# FEU-102-1_part1.net
KiCad netlist of a schematic drawn in Altium Designer
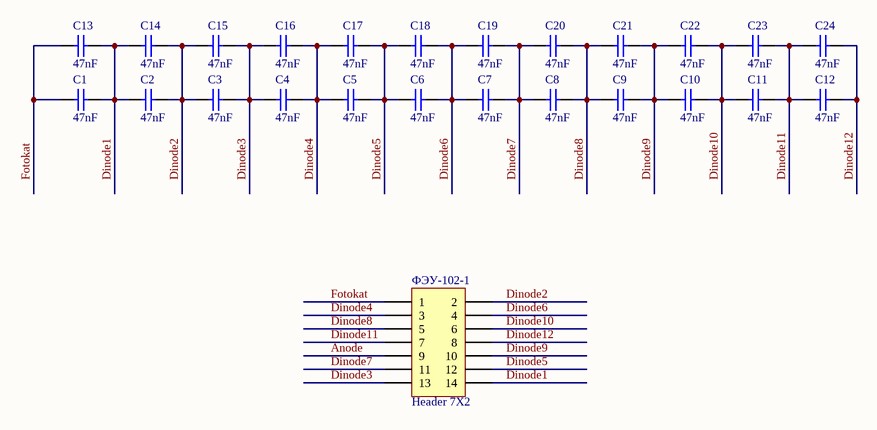
[diagram p0: FEU-102-1_part1.SchDoc]

(export (version "E")
  (design (tool "Eeschema 10.0.6"))
  (components
    (comp (ref "C1")
      (value "47nF")
      (footprint "0805_CAP")
      (description "Capacitor (Semiconductor SIM Model)")
      (fields (field (name "PUBLISHER") "Altium Limited"))
      (libsource (lib "Miscellaneous Devices") (part "Cap Semi"))
    )
    (comp (ref "C2")
      (value "47nF")
      (footprint "0805_CAP")
      (description "Capacitor (Semiconductor SIM Model)")
      (fields (field (name "PUBLISHER") "Altium Limited"))
      (libsource (lib "Miscellaneous Devices") (part "Cap Semi"))
    )
    (comp (ref "C3")
      (value "47nF")
      (footprint "0805_CAP")
      (description "Capacitor (Semiconductor SIM Model)")
      (fields (field (name "PUBLISHER") "Altium Limited"))
      (libsource (lib "Miscellaneous Devices") (part "Cap Semi"))
    )
    (comp (ref "C4")
      (value "47nF")
      (footprint "0805_CAP")
      (description "Capacitor (Semiconductor SIM Model)")
      (fields (field (name "PUBLISHER") "Altium Limited"))
      (libsource (lib "Miscellaneous Devices") (part "Cap Semi"))
    )
    (comp (ref "C5")
      (value "47nF")
      (footprint "0805_CAP")
      (description "Capacitor (Semiconductor SIM Model)")
      (fields (field (name "PUBLISHER") "Altium Limited"))
      (libsource (lib "Miscellaneous Devices") (part "Cap Semi"))
    )
    (comp (ref "C6")
      (value "47nF")
      (footprint "0805_CAP")
      (description "Capacitor (Semiconductor SIM Model)")
      (fields (field (name "PUBLISHER") "Altium Limited"))
      (libsource (lib "Miscellaneous Devices") (part "Cap Semi"))
    )
    (comp (ref "C7")
      (value "47nF")
      (footprint "0805_CAP")
      (description "Capacitor (Semiconductor SIM Model)")
      (fields (field (name "PUBLISHER") "Altium Limited"))
      (libsource (lib "Miscellaneous Devices") (part "Cap Semi"))
    )
    (comp (ref "C8")
      (value "47nF")
      (footprint "0805_CAP")
      (description "Capacitor (Semiconductor SIM Model)")
      (fields (field (name "PUBLISHER") "Altium Limited"))
      (libsource (lib "Miscellaneous Devices") (part "Cap Semi"))
    )
    (comp (ref "C9")
      (value "47nF")
      (footprint "0805_CAP")
      (description "Capacitor (Semiconductor SIM Model)")
      (fields (field (name "PUBLISHER") "Altium Limited"))
      (libsource (lib "Miscellaneous Devices") (part "Cap Semi"))
    )
    (comp (ref "C10")
      (value "47nF")
      (footprint "0805_CAP")
      (description "Capacitor (Semiconductor SIM Model)")
      (fields (field (name "PUBLISHER") "Altium Limited"))
      (libsource (lib "Miscellaneous Devices") (part "Cap Semi"))
    )
    (comp (ref "C11")
      (value "47nF")
      (footprint "0805_CAP")
      (description "Capacitor (Semiconductor SIM Model)")
      (fields (field (name "PUBLISHER") "Altium Limited"))
      (libsource (lib "Miscellaneous Devices") (part "Cap Semi"))
    )
    (comp (ref "C12")
      (value "47nF")
      (footprint "0805_CAP")
      (description "Capacitor (Semiconductor SIM Model)")
      (fields (field (name "PUBLISHER") "Altium Limited"))
      (libsource (lib "Miscellaneous Devices") (part "Cap Semi"))
    )
    (comp (ref "C13")
      (value "47nF")
      (footprint "0805_CAP")
      (description "Capacitor (Semiconductor SIM Model)")
      (fields (field (name "PUBLISHER") "Altium Limited"))
      (libsource (lib "Miscellaneous Devices") (part "Cap Semi"))
    )
    (comp (ref "C14")
      (value "47nF")
      (footprint "0805_CAP")
      (description "Capacitor (Semiconductor SIM Model)")
      (fields (field (name "PUBLISHER") "Altium Limited"))
      (libsource (lib "Miscellaneous Devices") (part "Cap Semi"))
    )
    (comp (ref "C15")
      (value "47nF")
      (footprint "0805_CAP")
      (description "Capacitor (Semiconductor SIM Model)")
      (fields (field (name "PUBLISHER") "Altium Limited"))
      (libsource (lib "Miscellaneous Devices") (part "Cap Semi"))
    )
    (comp (ref "C16")
      (value "47nF")
      (footprint "0805_CAP")
      (description "Capacitor (Semiconductor SIM Model)")
      (fields (field (name "PUBLISHER") "Altium Limited"))
      (libsource (lib "Miscellaneous Devices") (part "Cap Semi"))
    )
    (comp (ref "C17")
      (value "47nF")
      (footprint "0805_CAP")
      (description "Capacitor (Semiconductor SIM Model)")
      (fields (field (name "PUBLISHER") "Altium Limited"))
      (libsource (lib "Miscellaneous Devices") (part "Cap Semi"))
    )
    (comp (ref "C18")
      (value "47nF")
      (footprint "0805_CAP")
      (description "Capacitor (Semiconductor SIM Model)")
      (fields (field (name "PUBLISHER") "Altium Limited"))
      (libsource (lib "Miscellaneous Devices") (part "Cap Semi"))
    )
    (comp (ref "C19")
      (value "47nF")
      (footprint "0805_CAP")
      (description "Capacitor (Semiconductor SIM Model)")
      (fields (field (name "PUBLISHER") "Altium Limited"))
      (libsource (lib "Miscellaneous Devices") (part "Cap Semi"))
    )
    (comp (ref "C20")
      (value "47nF")
      (footprint "0805_CAP")
      (description "Capacitor (Semiconductor SIM Model)")
      (fields (field (name "PUBLISHER") "Altium Limited"))
      (libsource (lib "Miscellaneous Devices") (part "Cap Semi"))
    )
    (comp (ref "C21")
      (value "47nF")
      (footprint "0805_CAP")
      (description "Capacitor (Semiconductor SIM Model)")
      (fields (field (name "PUBLISHER") "Altium Limited"))
      (libsource (lib "Miscellaneous Devices") (part "Cap Semi"))
    )
    (comp (ref "C22")
      (value "47nF")
      (footprint "0805_CAP")
      (description "Capacitor (Semiconductor SIM Model)")
      (fields (field (name "PUBLISHER") "Altium Limited"))
      (libsource (lib "Miscellaneous Devices") (part "Cap Semi"))
    )
    (comp (ref "C23")
      (value "47nF")
      (footprint "0805_CAP")
      (description "Capacitor (Semiconductor SIM Model)")
      (fields (field (name "PUBLISHER") "Altium Limited"))
      (libsource (lib "Miscellaneous Devices") (part "Cap Semi"))
    )
    (comp (ref "C24")
      (value "47nF")
      (footprint "0805_CAP")
      (description "Capacitor (Semiconductor SIM Model)")
      (fields (field (name "PUBLISHER") "Altium Limited"))
      (libsource (lib "Miscellaneous Devices") (part "Cap Semi"))
    )
    (comp (ref "ФЭУ-102-1")
      (value "Header 7X2")
      (footprint "ФЭУ-102")
      (description "Header, 7-Pin, Dual row")
      (fields (field (name "PUBLISHER") "Altium Limited"))
      (libsource (lib "Miscellaneous Connectors") (part "Header 7X2"))
    )
  )
  (nets
    (net (code "1") (name "/Anode") (class "Default")
      (node (ref "ФЭУ-102-1") (pin "9") (pinfunction "9_9") (pintype "passive"))
    )
    (net (code "2") (name "/Dinode1") (class "Default")
      (node (ref "C1") (pin "1") (pinfunction "1_1") (pintype "passive"))
      (node (ref "C13") (pin "1") (pinfunction "1_1") (pintype "passive"))
      (node (ref "C14") (pin "2") (pinfunction "2_2") (pintype "passive"))
      (node (ref "C2") (pin "2") (pinfunction "2_2") (pintype "passive"))
      (node (ref "ФЭУ-102-1") (pin "14") (pinfunction "14_14") (pintype "passive"))
    )
    (net (code "3") (name "/Dinode2") (class "Default")
      (node (ref "C14") (pin "1") (pinfunction "1_1") (pintype "passive"))
      (node (ref "C15") (pin "2") (pinfunction "2_2") (pintype "passive"))
      (node (ref "C2") (pin "1") (pinfunction "1_1") (pintype "passive"))
      (node (ref "C3") (pin "2") (pinfunction "2_2") (pintype "passive"))
      (node (ref "ФЭУ-102-1") (pin "2") (pinfunction "2_2") (pintype "passive"))
    )
    (net (code "4") (name "/Dinode3") (class "Default")
      (node (ref "C15") (pin "1") (pinfunction "1_1") (pintype "passive"))
      (node (ref "C16") (pin "2") (pinfunction "2_2") (pintype "passive"))
      (node (ref "C3") (pin "1") (pinfunction "1_1") (pintype "passive"))
      (node (ref "C4") (pin "2") (pinfunction "2_2") (pintype "passive"))
      (node (ref "ФЭУ-102-1") (pin "13") (pinfunction "13_13") (pintype "passive"))
    )
    (net (code "5") (name "/Dinode4") (class "Default")
      (node (ref "C16") (pin "1") (pinfunction "1_1") (pintype "passive"))
      (node (ref "C17") (pin "2") (pinfunction "2_2") (pintype "passive"))
      (node (ref "C4") (pin "1") (pinfunction "1_1") (pintype "passive"))
      (node (ref "C5") (pin "2") (pinfunction "2_2") (pintype "passive"))
      (node (ref "ФЭУ-102-1") (pin "3") (pinfunction "3_3") (pintype "passive"))
    )
    (net (code "6") (name "/Dinode5") (class "Default")
      (node (ref "C17") (pin "1") (pinfunction "1_1") (pintype "passive"))
      (node (ref "C18") (pin "2") (pinfunction "2_2") (pintype "passive"))
      (node (ref "C5") (pin "1") (pinfunction "1_1") (pintype "passive"))
      (node (ref "C6") (pin "2") (pinfunction "2_2") (pintype "passive"))
      (node (ref "ФЭУ-102-1") (pin "12") (pinfunction "12_12") (pintype "passive"))
    )
    (net (code "7") (name "/Dinode6") (class "Default")
      (node (ref "C18") (pin "1") (pinfunction "1_1") (pintype "passive"))
      (node (ref "C19") (pin "2") (pinfunction "2_2") (pintype "passive"))
      (node (ref "C6") (pin "1") (pinfunction "1_1") (pintype "passive"))
      (node (ref "C7") (pin "2") (pinfunction "2_2") (pintype "passive"))
      (node (ref "ФЭУ-102-1") (pin "4") (pinfunction "4_4") (pintype "passive"))
    )
    (net (code "8") (name "/Dinode7") (class "Default")
      (node (ref "C19") (pin "1") (pinfunction "1_1") (pintype "passive"))
      (node (ref "C20") (pin "2") (pinfunction "2_2") (pintype "passive"))
      (node (ref "C7") (pin "1") (pinfunction "1_1") (pintype "passive"))
      (node (ref "C8") (pin "2") (pinfunction "2_2") (pintype "passive"))
      (node (ref "ФЭУ-102-1") (pin "11") (pinfunction "11_11") (pintype "passive"))
    )
    (net (code "9") (name "/Dinode8") (class "Default")
      (node (ref "C20") (pin "1") (pinfunction "1_1") (pintype "passive"))
      (node (ref "C21") (pin "2") (pinfunction "2_2") (pintype "passive"))
      (node (ref "C8") (pin "1") (pinfunction "1_1") (pintype "passive"))
      (node (ref "C9") (pin "2") (pinfunction "2_2") (pintype "passive"))
      (node (ref "ФЭУ-102-1") (pin "5") (pinfunction "5_5") (pintype "passive"))
    )
    (net (code "10") (name "/Dinode9") (class "Default")
      (node (ref "C10") (pin "2") (pinfunction "2_2") (pintype "passive"))
      (node (ref "C21") (pin "1") (pinfunction "1_1") (pintype "passive"))
      (node (ref "C22") (pin "2") (pinfunction "2_2") (pintype "passive"))
      (node (ref "C9") (pin "1") (pinfunction "1_1") (pintype "passive"))
      (node (ref "ФЭУ-102-1") (pin "10") (pinfunction "10_10") (pintype "passive"))
    )
    (net (code "11") (name "/Dinode10") (class "Default")
      (node (ref "C10") (pin "1") (pinfunction "1_1") (pintype "passive"))
      (node (ref "C11") (pin "2") (pinfunction "2_2") (pintype "passive"))
      (node (ref "C22") (pin "1") (pinfunction "1_1") (pintype "passive"))
      (node (ref "C23") (pin "2") (pinfunction "2_2") (pintype "passive"))
      (node (ref "ФЭУ-102-1") (pin "6") (pinfunction "6_6") (pintype "passive"))
    )
    (net (code "12") (name "/Dinode11") (class "Default")
      (node (ref "C11") (pin "1") (pinfunction "1_1") (pintype "passive"))
      (node (ref "C12") (pin "2") (pinfunction "2_2") (pintype "passive"))
      (node (ref "C23") (pin "1") (pinfunction "1_1") (pintype "passive"))
      (node (ref "C24") (pin "2") (pinfunction "2_2") (pintype "passive"))
      (node (ref "ФЭУ-102-1") (pin "7") (pinfunction "7_7") (pintype "passive"))
    )
    (net (code "13") (name "/Dinode12") (class "Default")
      (node (ref "C12") (pin "1") (pinfunction "1_1") (pintype "passive"))
      (node (ref "C24") (pin "1") (pinfunction "1_1") (pintype "passive"))
      (node (ref "ФЭУ-102-1") (pin "8") (pinfunction "8_8") (pintype "passive"))
    )
    (net (code "14") (name "/Fotokat") (class "Default")
      (node (ref "C1") (pin "2") (pinfunction "2_2") (pintype "passive"))
      (node (ref "C13") (pin "2") (pinfunction "2_2") (pintype "passive"))
      (node (ref "ФЭУ-102-1") (pin "1") (pinfunction "1_1") (pintype "passive"))
    )
  )
)
